# ACT_Lipoly_Charger_R3_FINAL.net
KiCad netlist of a schematic drawn in EAGLE
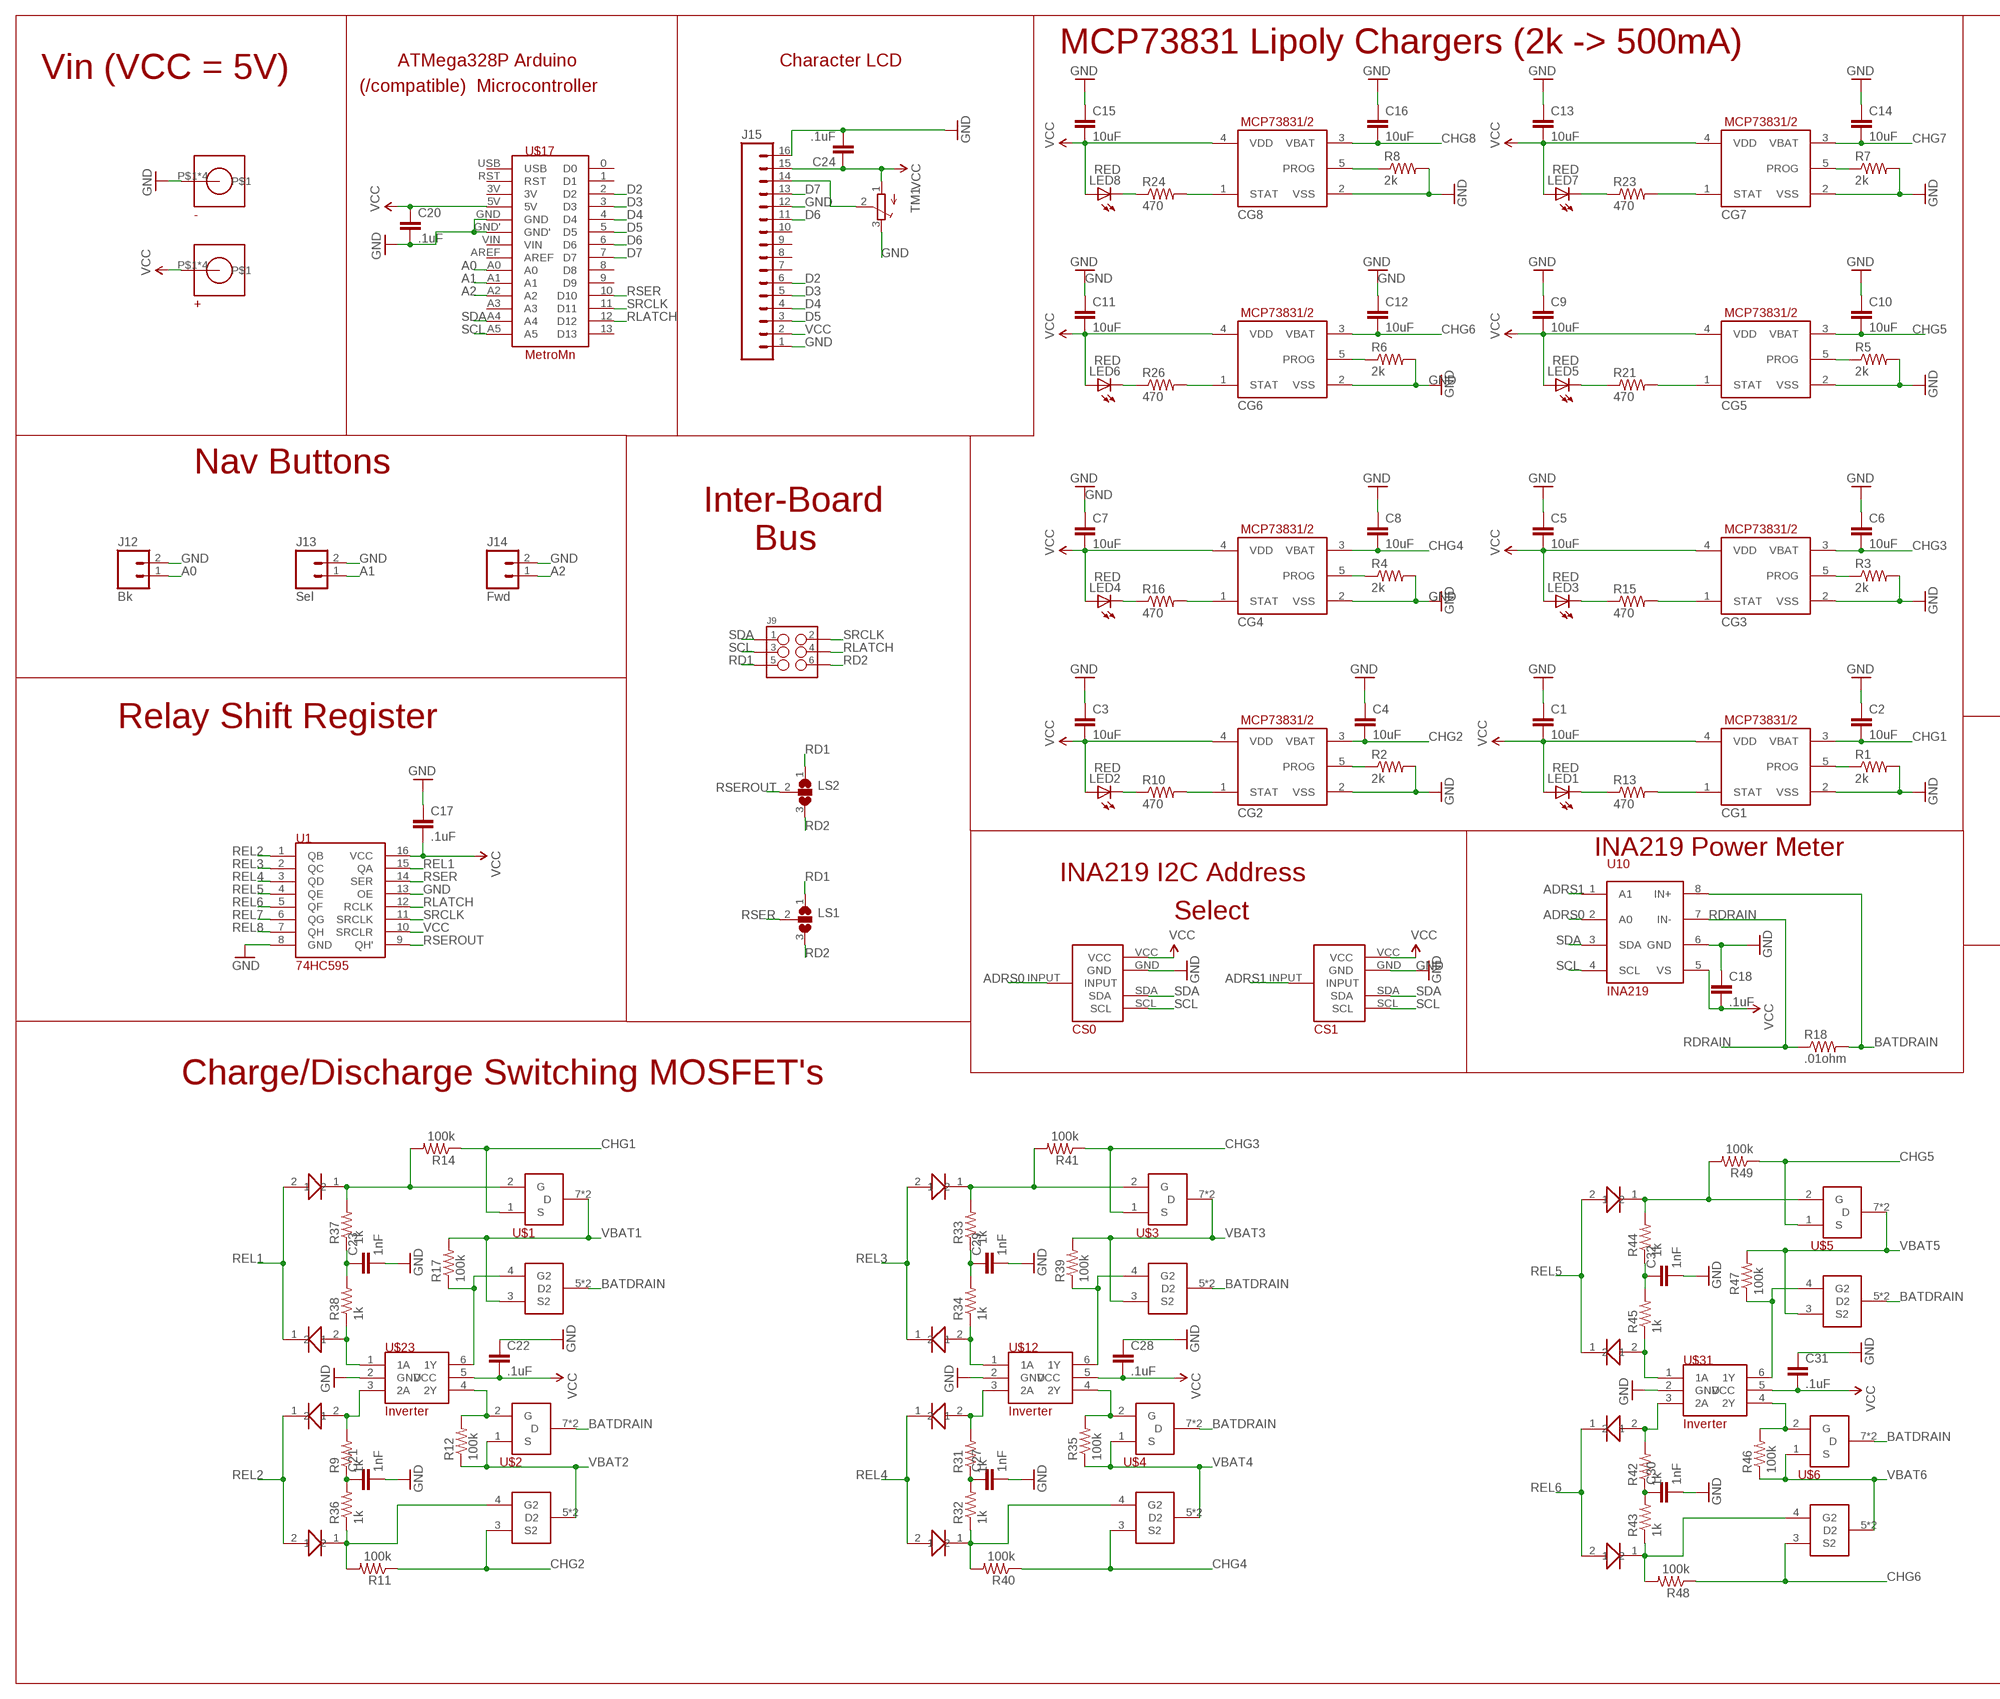
[diagram p0: schematic, sheet 1, part 1 of 2]
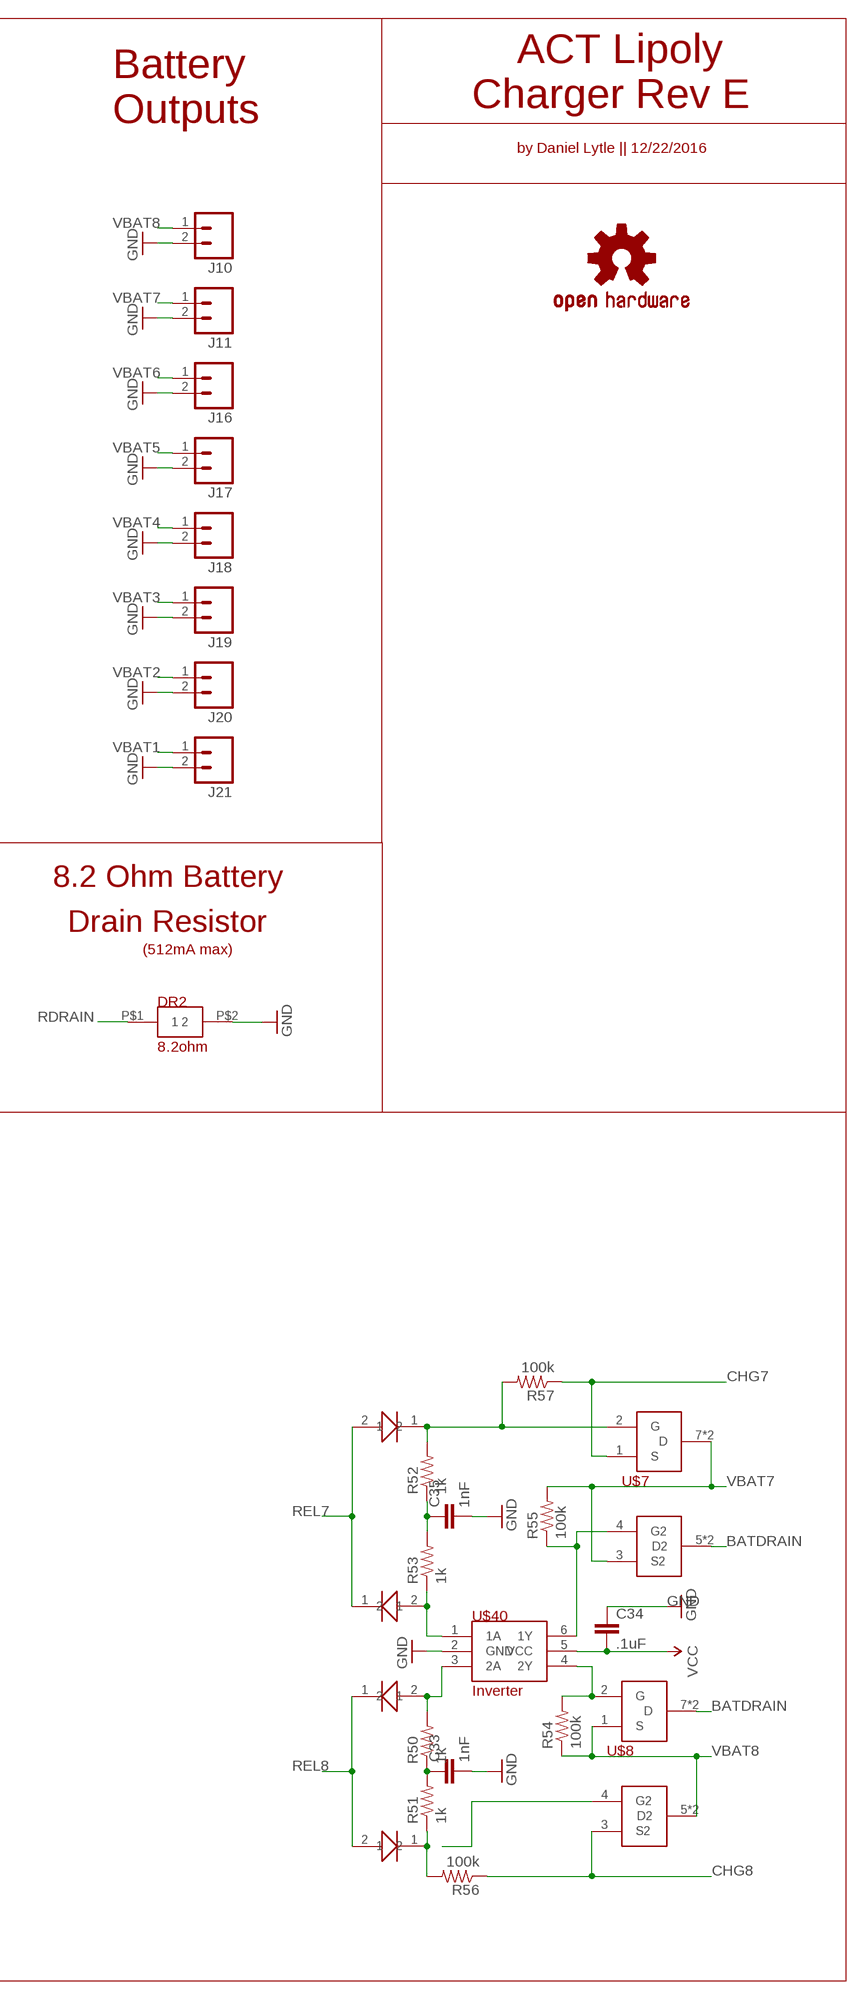
[diagram p1: schematic, sheet 1, part 2 of 2]

(export (version "E")
  (design (tool "Eeschema 10.0.6"))
  (components
    (comp (ref "+")
      (value "8191-SEMS")
      (footprint "eagle-import:9191-SEMS")
      (libsource (lib "eagle-import") (part "8191-SEMS"))
    )
    (comp (ref "-")
      (value "8191-SEMS")
      (footprint "eagle-import:9191-SEMS")
      (libsource (lib "eagle-import") (part "8191-SEMS"))
    )
    (comp (ref "C1")
      (value "10uF")
      (footprint "eagle-import:0805")
      (libsource (lib "eagle-import") (part "CAP0805"))
    )
    (comp (ref "C2")
      (value "10uF")
      (footprint "eagle-import:0805")
      (libsource (lib "eagle-import") (part "CAP0805"))
    )
    (comp (ref "C3")
      (value "10uF")
      (footprint "eagle-import:0805")
      (libsource (lib "eagle-import") (part "CAP0805"))
    )
    (comp (ref "C4")
      (value "10uF")
      (footprint "eagle-import:0805")
      (libsource (lib "eagle-import") (part "CAP0805"))
    )
    (comp (ref "C5")
      (value "10uF")
      (footprint "eagle-import:0805")
      (libsource (lib "eagle-import") (part "CAP0805"))
    )
    (comp (ref "C6")
      (value "10uF")
      (footprint "eagle-import:0805")
      (libsource (lib "eagle-import") (part "CAP0805"))
    )
    (comp (ref "C7")
      (value "10uF")
      (footprint "eagle-import:0805")
      (libsource (lib "eagle-import") (part "CAP0805"))
    )
    (comp (ref "C8")
      (value "10uF")
      (footprint "eagle-import:0805")
      (libsource (lib "eagle-import") (part "CAP0805"))
    )
    (comp (ref "C9")
      (value "10uF")
      (footprint "eagle-import:0805")
      (libsource (lib "eagle-import") (part "CAP0805"))
    )
    (comp (ref "C10")
      (value "10uF")
      (footprint "eagle-import:0805")
      (libsource (lib "eagle-import") (part "CAP0805"))
    )
    (comp (ref "C11")
      (value "10uF")
      (footprint "eagle-import:0805")
      (libsource (lib "eagle-import") (part "CAP0805"))
    )
    (comp (ref "C12")
      (value "10uF")
      (footprint "eagle-import:0805")
      (libsource (lib "eagle-import") (part "CAP0805"))
    )
    (comp (ref "C13")
      (value "10uF")
      (footprint "eagle-import:0805")
      (libsource (lib "eagle-import") (part "CAP0805"))
    )
    (comp (ref "C14")
      (value "10uF")
      (footprint "eagle-import:0805")
      (libsource (lib "eagle-import") (part "CAP0805"))
    )
    (comp (ref "C15")
      (value "10uF")
      (footprint "eagle-import:0805")
      (libsource (lib "eagle-import") (part "CAP0805"))
    )
    (comp (ref "C16")
      (value "10uF")
      (footprint "eagle-import:0805")
      (libsource (lib "eagle-import") (part "CAP0805"))
    )
    (comp (ref "C17")
      (value ".1uF")
      (footprint "eagle-import:0805")
      (libsource (lib "eagle-import") (part "CAP0805"))
    )
    (comp (ref "C18")
      (value ".1uF")
      (footprint "eagle-import:0805")
      (libsource (lib "eagle-import") (part "CAP0805"))
    )
    (comp (ref "C20")
      (value ".1uF")
      (footprint "eagle-import:0805")
      (libsource (lib "eagle-import") (part "CAP0805"))
    )
    (comp (ref "C21")
      (value "1nF")
      (footprint "eagle-import:0805")
      (libsource (lib "eagle-import") (part "SparkFun-Passives_CAP0805"))
    )
    (comp (ref "C22")
      (value ".1uF")
      (footprint "eagle-import:0805")
      (libsource (lib "eagle-import") (part "CAP0805"))
    )
    (comp (ref "C23")
      (value "1nF")
      (footprint "eagle-import:0805")
      (libsource (lib "eagle-import") (part "SparkFun-Passives_CAP0805"))
    )
    (comp (ref "C24")
      (value ".1uF")
      (footprint "eagle-import:0805")
      (libsource (lib "eagle-import") (part "CAP0805"))
    )
    (comp (ref "C27")
      (value "1nF")
      (footprint "eagle-import:0805")
      (libsource (lib "eagle-import") (part "SparkFun-Passives_CAP0805"))
    )
    (comp (ref "C28")
      (value ".1uF")
      (footprint "eagle-import:0805")
      (libsource (lib "eagle-import") (part "CAP0805"))
    )
    (comp (ref "C29")
      (value "1nF")
      (footprint "eagle-import:0805")
      (libsource (lib "eagle-import") (part "SparkFun-Passives_CAP0805"))
    )
    (comp (ref "C30")
      (value "1nF")
      (footprint "eagle-import:0805")
      (libsource (lib "eagle-import") (part "SparkFun-Passives_CAP0805"))
    )
    (comp (ref "C31")
      (value ".1uF")
      (footprint "eagle-import:0805")
      (libsource (lib "eagle-import") (part "CAP0805"))
    )
    (comp (ref "C32")
      (value "1nF")
      (footprint "eagle-import:0805")
      (libsource (lib "eagle-import") (part "SparkFun-Passives_CAP0805"))
    )
    (comp (ref "C33")
      (value "1nF")
      (footprint "eagle-import:0805")
      (libsource (lib "eagle-import") (part "SparkFun-Passives_CAP0805"))
    )
    (comp (ref "C34")
      (value ".1uF")
      (footprint "eagle-import:0805")
      (libsource (lib "eagle-import") (part "CAP0805"))
    )
    (comp (ref "C35")
      (value "1nF")
      (footprint "eagle-import:0805")
      (libsource (lib "eagle-import") (part "SparkFun-Passives_CAP0805"))
    )
    (comp (ref "CG1")
      (value "MCP73831/OT")
      (footprint "eagle-import:SOT23-5L")
      (libsource (lib "eagle-import") (part "MCP73831/OT"))
    )
    (comp (ref "CG2")
      (value "MCP73831/OT")
      (footprint "eagle-import:SOT23-5L")
      (libsource (lib "eagle-import") (part "MCP73831/OT"))
    )
    (comp (ref "CG3")
      (value "MCP73831/OT")
      (footprint "eagle-import:SOT23-5L")
      (libsource (lib "eagle-import") (part "MCP73831/OT"))
    )
    (comp (ref "CG4")
      (value "MCP73831/OT")
      (footprint "eagle-import:SOT23-5L")
      (libsource (lib "eagle-import") (part "MCP73831/OT"))
    )
    (comp (ref "CG5")
      (value "MCP73831/OT")
      (footprint "eagle-import:SOT23-5L")
      (libsource (lib "eagle-import") (part "MCP73831/OT"))
    )
    (comp (ref "CG6")
      (value "MCP73831/OT")
      (footprint "eagle-import:SOT23-5L")
      (libsource (lib "eagle-import") (part "MCP73831/OT"))
    )
    (comp (ref "CG7")
      (value "MCP73831/OT")
      (footprint "eagle-import:SOT23-5L")
      (libsource (lib "eagle-import") (part "MCP73831/OT"))
    )
    (comp (ref "CG8")
      (value "MCP73831/OT")
      (footprint "eagle-import:SOT23-5L")
      (libsource (lib "eagle-import") (part "MCP73831/OT"))
    )
    (comp (ref "CS0")
      (value "4-WAYSELECTOR")
      (footprint "eagle-import:4-WAYSELECTOR")
      (libsource (lib "eagle-import") (part "4-WAYSELECTOR"))
    )
    (comp (ref "CS1")
      (value "4-WAYSELECTOR")
      (footprint "eagle-import:4-WAYSELECTOR")
      (libsource (lib "eagle-import") (part "4-WAYSELECTOR"))
    )
    (comp (ref "DR2")
      (value "8.2ohm")
      (footprint "eagle-import:UB5C-5R6F1")
      (libsource (lib "eagle-import") (part "UB5C-5R6F1"))
    )
    (comp (ref "J9")
      (value "M03X2FEMALE")
      (footprint "eagle-import:2X3")
      (libsource (lib "eagle-import") (part "M03X2FEMALE"))
    )
    (comp (ref "J10")
      (value "M02LOCK_LONGPADS")
      (footprint "eagle-import:1X02_LOCK_LONGPADS")
      (libsource (lib "eagle-import") (part "M02LOCK_LONGPADS"))
    )
    (comp (ref "J11")
      (value "M02LOCK_LONGPADS")
      (footprint "eagle-import:1X02_LOCK_LONGPADS")
      (libsource (lib "eagle-import") (part "M02LOCK_LONGPADS"))
    )
    (comp (ref "J12")
      (value "Bk")
      (footprint "eagle-import:1X02_LOCK_LONGPADS")
      (libsource (lib "eagle-import") (part "M02LOCK_LONGPADS"))
    )
    (comp (ref "J13")
      (value "Sel")
      (footprint "eagle-import:1X02_LOCK_LONGPADS")
      (libsource (lib "eagle-import") (part "M02LOCK_LONGPADS"))
    )
    (comp (ref "J14")
      (value "Fwd")
      (footprint "eagle-import:1X02_LOCK_LONGPADS")
      (libsource (lib "eagle-import") (part "M02LOCK_LONGPADS"))
    )
    (comp (ref "J15")
      (value "M16LOCK_LONGPADS")
      (footprint "eagle-import:1X16_LOCK_LONGPADS")
      (libsource (lib "eagle-import") (part "M16LOCK_LONGPADS"))
    )
    (comp (ref "J16")
      (value "M02LOCK_LONGPADS")
      (footprint "eagle-import:1X02_LOCK_LONGPADS")
      (libsource (lib "eagle-import") (part "M02LOCK_LONGPADS"))
    )
    (comp (ref "J17")
      (value "M02LOCK_LONGPADS")
      (footprint "eagle-import:1X02_LOCK_LONGPADS")
      (libsource (lib "eagle-import") (part "M02LOCK_LONGPADS"))
    )
    (comp (ref "J18")
      (value "M02LOCK_LONGPADS")
      (footprint "eagle-import:1X02_LOCK_LONGPADS")
      (libsource (lib "eagle-import") (part "M02LOCK_LONGPADS"))
    )
    (comp (ref "J19")
      (value "M02LOCK_LONGPADS")
      (footprint "eagle-import:1X02_LOCK_LONGPADS")
      (libsource (lib "eagle-import") (part "M02LOCK_LONGPADS"))
    )
    (comp (ref "J20")
      (value "M02LOCK_LONGPADS")
      (footprint "eagle-import:1X02_LOCK_LONGPADS")
      (libsource (lib "eagle-import") (part "M02LOCK_LONGPADS"))
    )
    (comp (ref "J21")
      (value "M02LOCK_LONGPADS")
      (footprint "eagle-import:1X02_LOCK_LONGPADS")
      (libsource (lib "eagle-import") (part "M02LOCK_LONGPADS"))
    )
    (comp (ref "LED1")
      (value "RED")
      (footprint "eagle-import:CHIP-LED0805")
      (libsource (lib "eagle-import") (part "LEDCHIP-LED0805"))
    )
    (comp (ref "LED2")
      (value "RED")
      (footprint "eagle-import:CHIP-LED0805")
      (libsource (lib "eagle-import") (part "LEDCHIP-LED0805"))
    )
    (comp (ref "LED3")
      (value "RED")
      (footprint "eagle-import:CHIP-LED0805")
      (libsource (lib "eagle-import") (part "LEDCHIP-LED0805"))
    )
    (comp (ref "LED4")
      (value "RED")
      (footprint "eagle-import:CHIP-LED0805")
      (libsource (lib "eagle-import") (part "LEDCHIP-LED0805"))
    )
    (comp (ref "LED5")
      (value "RED")
      (footprint "eagle-import:CHIP-LED0805")
      (libsource (lib "eagle-import") (part "LEDCHIP-LED0805"))
    )
    (comp (ref "LED6")
      (value "RED")
      (footprint "eagle-import:CHIP-LED0805")
      (libsource (lib "eagle-import") (part "LEDCHIP-LED0805"))
    )
    (comp (ref "LED7")
      (value "RED")
      (footprint "eagle-import:CHIP-LED0805")
      (libsource (lib "eagle-import") (part "LEDCHIP-LED0805"))
    )
    (comp (ref "LED8")
      (value "RED")
      (footprint "eagle-import:CHIP-LED0805")
      (libsource (lib "eagle-import") (part "LEDCHIP-LED0805"))
    )
    (comp (ref "LS1")
      (value "SJ2W")
      (footprint "eagle-import:SJ_2")
      (libsource (lib "eagle-import") (part "SJ2W"))
    )
    (comp (ref "LS2")
      (value "SJ2W")
      (footprint "eagle-import:SJ_2")
      (libsource (lib "eagle-import") (part "SJ2W"))
    )
    (comp (ref "R1")
      (value "2k")
      (footprint "eagle-import:0805")
      (libsource (lib "eagle-import") (part "RESISTOR0805-RES"))
    )
    (comp (ref "R2")
      (value "2k")
      (footprint "eagle-import:0805")
      (libsource (lib "eagle-import") (part "RESISTOR0805-RES"))
    )
    (comp (ref "R3")
      (value "2k")
      (footprint "eagle-import:0805")
      (libsource (lib "eagle-import") (part "RESISTOR0805-RES"))
    )
    (comp (ref "R4")
      (value "2k")
      (footprint "eagle-import:0805")
      (libsource (lib "eagle-import") (part "RESISTOR0805-RES"))
    )
    (comp (ref "R5")
      (value "2k")
      (footprint "eagle-import:0805")
      (libsource (lib "eagle-import") (part "RESISTOR0805-RES"))
    )
    (comp (ref "R6")
      (value "2k")
      (footprint "eagle-import:0805")
      (libsource (lib "eagle-import") (part "RESISTOR0805-RES"))
    )
    (comp (ref "R7")
      (value "2k")
      (footprint "eagle-import:0805")
      (libsource (lib "eagle-import") (part "RESISTOR0805-RES"))
    )
    (comp (ref "R8")
      (value "2k")
      (footprint "eagle-import:0805")
      (libsource (lib "eagle-import") (part "RESISTOR0805-RES"))
    )
    (comp (ref "R9")
      (value "1k")
      (footprint "eagle-import:0805")
      (libsource (lib "eagle-import") (part "SparkFun-Resistors_RESISTOR0805-RES"))
    )
    (comp (ref "R10")
      (value "470")
      (footprint "eagle-import:0805")
      (libsource (lib "eagle-import") (part "RESISTOR0805-RES"))
    )
    (comp (ref "R11")
      (value "100k")
      (footprint "eagle-import:0805")
      (libsource (lib "eagle-import") (part "RESISTOR0805-RES"))
    )
    (comp (ref "R12")
      (value "100k")
      (footprint "eagle-import:0805")
      (libsource (lib "eagle-import") (part "RESISTOR0805-RES"))
    )
    (comp (ref "R13")
      (value "470")
      (footprint "eagle-import:0805")
      (libsource (lib "eagle-import") (part "RESISTOR0805-RES"))
    )
    (comp (ref "R14")
      (value "100k")
      (footprint "eagle-import:0805")
      (libsource (lib "eagle-import") (part "RESISTOR0805-RES"))
    )
    (comp (ref "R15")
      (value "470")
      (footprint "eagle-import:0805")
      (libsource (lib "eagle-import") (part "RESISTOR0805-RES"))
    )
    (comp (ref "R16")
      (value "470")
      (footprint "eagle-import:0805")
      (libsource (lib "eagle-import") (part "RESISTOR0805-RES"))
    )
    (comp (ref "R17")
      (value "100k")
      (footprint "eagle-import:0805")
      (libsource (lib "eagle-import") (part "RESISTOR0805-RES"))
    )
    (comp (ref "R18")
      (value ".01ohm")
      (footprint "eagle-import:0805")
      (libsource (lib "eagle-import") (part "RESISTOR0805-RES"))
    )
    (comp (ref "R21")
      (value "470")
      (footprint "eagle-import:0805")
      (libsource (lib "eagle-import") (part "RESISTOR0805-RES"))
    )
    (comp (ref "R23")
      (value "470")
      (footprint "eagle-import:0805")
      (libsource (lib "eagle-import") (part "RESISTOR0805-RES"))
    )
    (comp (ref "R24")
      (value "470")
      (footprint "eagle-import:0805")
      (libsource (lib "eagle-import") (part "RESISTOR0805-RES"))
    )
    (comp (ref "R26")
      (value "470")
      (footprint "eagle-import:0805")
      (libsource (lib "eagle-import") (part "RESISTOR0805-RES"))
    )
    (comp (ref "R31")
      (value "1k")
      (footprint "eagle-import:0805")
      (libsource (lib "eagle-import") (part "SparkFun-Resistors_RESISTOR0805-RES"))
    )
    (comp (ref "R32")
      (value "1k")
      (footprint "eagle-import:0805")
      (libsource (lib "eagle-import") (part "SparkFun-Resistors_RESISTOR0805-RES"))
    )
    (comp (ref "R33")
      (value "1k")
      (footprint "eagle-import:0805")
      (libsource (lib "eagle-import") (part "SparkFun-Resistors_RESISTOR0805-RES"))
    )
    (comp (ref "R34")
      (value "1k")
      (footprint "eagle-import:0805")
      (libsource (lib "eagle-import") (part "SparkFun-Resistors_RESISTOR0805-RES"))
    )
    (comp (ref "R35")
      (value "100k")
      (footprint "eagle-import:0805")
      (libsource (lib "eagle-import") (part "RESISTOR0805-RES"))
    )
    (comp (ref "R36")
      (value "1k")
      (footprint "eagle-import:0805")
      (libsource (lib "eagle-import") (part "SparkFun-Resistors_RESISTOR0805-RES"))
    )
    (comp (ref "R37")
      (value "1k")
      (footprint "eagle-import:0805")
      (libsource (lib "eagle-import") (part "SparkFun-Resistors_RESISTOR0805-RES"))
    )
    (comp (ref "R38")
      (value "1k")
      (footprint "eagle-import:0805")
      (libsource (lib "eagle-import") (part "SparkFun-Resistors_RESISTOR0805-RES"))
    )
    (comp (ref "R39")
      (value "100k")
      (footprint "eagle-import:0805")
      (libsource (lib "eagle-import") (part "RESISTOR0805-RES"))
    )
    (comp (ref "R40")
      (value "100k")
      (footprint "eagle-import:0805")
      (libsource (lib "eagle-import") (part "RESISTOR0805-RES"))
    )
    (comp (ref "R41")
      (value "100k")
      (footprint "eagle-import:0805")
      (libsource (lib "eagle-import") (part "RESISTOR0805-RES"))
    )
    (comp (ref "R42")
      (value "1k")
      (footprint "eagle-import:0805")
      (libsource (lib "eagle-import") (part "SparkFun-Resistors_RESISTOR0805-RES"))
    )
    (comp (ref "R43")
      (value "1k")
      (footprint "eagle-import:0805")
      (libsource (lib "eagle-import") (part "SparkFun-Resistors_RESISTOR0805-RES"))
    )
    (comp (ref "R44")
      (value "1k")
      (footprint "eagle-import:0805")
      (libsource (lib "eagle-import") (part "SparkFun-Resistors_RESISTOR0805-RES"))
    )
    (comp (ref "R45")
      (value "1k")
      (footprint "eagle-import:0805")
      (libsource (lib "eagle-import") (part "SparkFun-Resistors_RESISTOR0805-RES"))
    )
    (comp (ref "R46")
      (value "100k")
      (footprint "eagle-import:0805")
      (libsource (lib "eagle-import") (part "RESISTOR0805-RES"))
    )
    (comp (ref "R47")
      (value "100k")
      (footprint "eagle-import:0805")
      (libsource (lib "eagle-import") (part "RESISTOR0805-RES"))
    )
    (comp (ref "R48")
      (value "100k")
      (footprint "eagle-import:0805")
      (libsource (lib "eagle-import") (part "RESISTOR0805-RES"))
    )
    (comp (ref "R49")
      (value "100k")
      (footprint "eagle-import:0805")
      (libsource (lib "eagle-import") (part "RESISTOR0805-RES"))
    )
    (comp (ref "R50")
      (value "1k")
      (footprint "eagle-import:0805")
      (libsource (lib "eagle-import") (part "SparkFun-Resistors_RESISTOR0805-RES"))
    )
    (comp (ref "R51")
      (value "1k")
      (footprint "eagle-import:0805")
      (libsource (lib "eagle-import") (part "SparkFun-Resistors_RESISTOR0805-RES"))
    )
    (comp (ref "R52")
      (value "1k")
      (footprint "eagle-import:0805")
      (libsource (lib "eagle-import") (part "SparkFun-Resistors_RESISTOR0805-RES"))
    )
    (comp (ref "R53")
      (value "1k")
      (footprint "eagle-import:0805")
      (libsource (lib "eagle-import") (part "SparkFun-Resistors_RESISTOR0805-RES"))
    )
    (comp (ref "R54")
      (value "100k")
      (footprint "eagle-import:0805")
      (libsource (lib "eagle-import") (part "RESISTOR0805-RES"))
    )
    (comp (ref "R55")
      (value "100k")
      (footprint "eagle-import:0805")
      (libsource (lib "eagle-import") (part "RESISTOR0805-RES"))
    )
    (comp (ref "R56")
      (value "100k")
      (footprint "eagle-import:0805")
      (libsource (lib "eagle-import") (part "RESISTOR0805-RES"))
    )
    (comp (ref "R57")
      (value "100k")
      (footprint "eagle-import:0805")
      (libsource (lib "eagle-import") (part "RESISTOR0805-RES"))
    )
    (comp (ref "TM1")
      (value "TRIMPOTTC33X")
      (footprint "eagle-import:TC33X")
      (libsource (lib "eagle-import") (part "TRIMPOTTC33X"))
    )
    (comp (ref "U$1")
      (value "DMP3085LSD")
      (footprint "eagle-import:SOIC8")
      (libsource (lib "eagle-import") (part "DMP3085LSD"))
    )
    (comp (ref "U$2")
      (value "DMP3085LSD")
      (footprint "eagle-import:SOIC8")
      (libsource (lib "eagle-import") (part "DMP3085LSD"))
    )
    (comp (ref "U$3")
      (value "DMP3085LSD")
      (footprint "eagle-import:SOIC8")
      (libsource (lib "eagle-import") (part "DMP3085LSD"))
    )
    (comp (ref "U$4")
      (value "DMP3085LSD")
      (footprint "eagle-import:SOIC8")
      (libsource (lib "eagle-import") (part "DMP3085LSD"))
    )
    (comp (ref "U$5")
      (value "DMP3085LSD")
      (footprint "eagle-import:SOIC8")
      (libsource (lib "eagle-import") (part "DMP3085LSD"))
    )
    (comp (ref "U$6")
      (value "DMP3085LSD")
      (footprint "eagle-import:SOIC8")
      (libsource (lib "eagle-import") (part "DMP3085LSD"))
    )
    (comp (ref "U$7")
      (value "DMP3085LSD")
      (footprint "eagle-import:SOIC8")
      (libsource (lib "eagle-import") (part "DMP3085LSD"))
    )
    (comp (ref "U$8")
      (value "DMP3085LSD")
      (footprint "eagle-import:SOIC8")
      (libsource (lib "eagle-import") (part "DMP3085LSD"))
    )
    (comp (ref "U$12")
      (value "Inverter")
      (footprint "eagle-import:SOT363_PHILIPS")
      (libsource (lib "eagle-import") (part "TC7PZ14FU,LJ(CT_INVERTER"))
    )
    (comp (ref "U$15")
      (value "DA2J10100L_DIODE")
      (footprint "eagle-import:SOD323")
      (libsource (lib "eagle-import") (part "DA2J10100L_DIODE"))
    )
    (comp (ref "U$16")
      (value "DA2J10100L_DIODE")
      (footprint "eagle-import:SOD323")
      (libsource (lib "eagle-import") (part "DA2J10100L_DIODE"))
    )
    (comp (ref "U$17")
      (value "MetroMn")
      (footprint "eagle-import:ADAFRUIT_METRO_MINI")
      (libsource (lib "eagle-import") (part "ADAFRUIT_METRO_MINI"))
    )
    (comp (ref "U$18")
      (value "DA2J10100L_DIODE")
      (footprint "eagle-import:SOD323")
      (libsource (lib "eagle-import") (part "DA2J10100L_DIODE"))
    )
    (comp (ref "U$19")
      (value "DA2J10100L_DIODE")
      (footprint "eagle-import:SOD323")
      (libsource (lib "eagle-import") (part "DA2J10100L_DIODE"))
    )
    (comp (ref "U$23")
      (value "Inverter")
      (footprint "eagle-import:SOT363_PHILIPS")
      (libsource (lib "eagle-import") (part "TC7PZ14FU,LJ(CT_INVERTER"))
    )
    (comp (ref "U$26")
      (value "DA2J10100L_DIODE")
      (footprint "eagle-import:SOD323")
      (libsource (lib "eagle-import") (part "DA2J10100L_DIODE"))
    )
    (comp (ref "U$27")
      (value "DA2J10100L_DIODE")
      (footprint "eagle-import:SOD323")
      (libsource (lib "eagle-import") (part "DA2J10100L_DIODE"))
    )
    (comp (ref "U$28")
      (value "DA2J10100L_DIODE")
      (footprint "eagle-import:SOD323")
      (libsource (lib "eagle-import") (part "DA2J10100L_DIODE"))
    )
    (comp (ref "U$29")
      (value "DA2J10100L_DIODE")
      (footprint "eagle-import:SOD323")
      (libsource (lib "eagle-import") (part "DA2J10100L_DIODE"))
    )
    (comp (ref "U$31")
      (value "Inverter")
      (footprint "eagle-import:SOT363_PHILIPS")
      (libsource (lib "eagle-import") (part "TC7PZ14FU,LJ(CT_INVERTER"))
    )
    (comp (ref "U$34")
      (value "DA2J10100L_DIODE")
      (footprint "eagle-import:SOD323")
      (libsource (lib "eagle-import") (part "DA2J10100L_DIODE"))
    )
    (comp (ref "U$35")
      (value "DA2J10100L_DIODE")
      (footprint "eagle-import:SOD323")
      (libsource (lib "eagle-import") (part "DA2J10100L_DIODE"))
    )
    (comp (ref "U$36")
      (value "DA2J10100L_DIODE")
      (footprint "eagle-import:SOD323")
      (libsource (lib "eagle-import") (part "DA2J10100L_DIODE"))
    )
    (comp (ref "U$37")
      (value "DA2J10100L_DIODE")
      (footprint "eagle-import:SOD323")
      (libsource (lib "eagle-import") (part "DA2J10100L_DIODE"))
    )
    (comp (ref "U$40")
      (value "Inverter")
      (footprint "eagle-import:SOT363_PHILIPS")
      (libsource (lib "eagle-import") (part "TC7PZ14FU,LJ(CT_INVERTER"))
    )
    (comp (ref "U$43")
      (value "DA2J10100L_DIODE")
      (footprint "eagle-import:SOD323")
      (libsource (lib "eagle-import") (part "DA2J10100L_DIODE"))
    )
    (comp (ref "U$44")
      (value "DA2J10100L_DIODE")
      (footprint "eagle-import:SOD323")
      (libsource (lib "eagle-import") (part "DA2J10100L_DIODE"))
    )
    (comp (ref "U$45")
      (value "DA2J10100L_DIODE")
      (footprint "eagle-import:SOD323")
      (libsource (lib "eagle-import") (part "DA2J10100L_DIODE"))
    )
    (comp (ref "U$46")
      (value "DA2J10100L_DIODE")
      (footprint "eagle-import:SOD323")
      (libsource (lib "eagle-import") (part "DA2J10100L_DIODE"))
    )
    (comp (ref "U1")
      (value "74HC595")
      (footprint "eagle-import:DIL16")
      (libsource (lib "eagle-import") (part "74HC595"))
    )
    (comp (ref "U10")
      (value "INA219")
      (footprint "eagle-import:SOIC8")
      (libsource (lib "eagle-import") (part "INA219"))
    )
    (comp (ref "VCC")
      (value "OSHW-LOGOM-COPPER")
      (footprint "eagle-import:OSHW-LOGO-M_COPPER")
      (libsource (lib "eagle-import") (part "OSHW-LOGOM-COPPER"))
    )
  )
  (nets
    (net (code "1") (name "/A0") (class "Default")
      (node (ref "J12") (pin "1") (pinfunction "1_1") (pintype "passive"))
      (node (ref "U$17") (pin "A0") (pinfunction "A0_A0") (pintype "bidirectional"))
    )
    (net (code "2") (name "/A1") (class "Default")
      (node (ref "J13") (pin "1") (pinfunction "1_1") (pintype "passive"))
      (node (ref "U$17") (pin "A1") (pinfunction "A1_A1") (pintype "bidirectional"))
    )
    (net (code "3") (name "/A2") (class "Default")
      (node (ref "J14") (pin "1") (pinfunction "1_1") (pintype "passive"))
      (node (ref "U$17") (pin "A2") (pinfunction "A2_A2") (pintype "bidirectional"))
    )
    (net (code "4") (name "/ADRS0") (class "Default")
      (node (ref "CS0") (pin "INPUT") (pinfunction "INPUT_INPUT") (pintype "bidirectional"))
      (node (ref "U10") (pin "2") (pinfunction "A0_2") (pintype "input"))
    )
    (net (code "5") (name "/ADRS1") (class "Default")
      (node (ref "CS1") (pin "INPUT") (pinfunction "INPUT_INPUT") (pintype "bidirectional"))
      (node (ref "U10") (pin "1") (pinfunction "A1_1") (pintype "input"))
    )
    (net (code "6") (name "/BATDRAIN") (class "Default")
      (node (ref "R18") (pin "2") (pinfunction "2_2") (pintype "passive"))
      (node (ref "U$1") (pin "5") (pinfunction "D2_5") (pintype "bidirectional"))
      (node (ref "U$1") (pin "6") (pinfunction "D2_6") (pintype "bidirectional"))
      (node (ref "U$2") (pin "7") (pinfunction "D_7") (pintype "bidirectional"))
      (node (ref "U$2") (pin "8") (pinfunction "D_8") (pintype "bidirectional"))
      (node (ref "U$3") (pin "5") (pinfunction "D2_5") (pintype "bidirectional"))
      (node (ref "U$3") (pin "6") (pinfunction "D2_6") (pintype "bidirectional"))
      (node (ref "U$4") (pin "7") (pinfunction "D_7") (pintype "bidirectional"))
      (node (ref "U$4") (pin "8") (pinfunction "D_8") (pintype "bidirectional"))
      (node (ref "U$5") (pin "5") (pinfunction "D2_5") (pintype "bidirectional"))
      (node (ref "U$5") (pin "6") (pinfunction "D2_6") (pintype "bidirectional"))
      (node (ref "U$6") (pin "7") (pinfunction "D_7") (pintype "bidirectional"))
      (node (ref "U$6") (pin "8") (pinfunction "D_8") (pintype "bidirectional"))
      (node (ref "U$7") (pin "5") (pinfunction "D2_5") (pintype "bidirectional"))
      (node (ref "U$7") (pin "6") (pinfunction "D2_6") (pintype "bidirectional"))
      (node (ref "U$8") (pin "7") (pinfunction "D_7") (pintype "bidirectional"))
      (node (ref "U$8") (pin "8") (pinfunction "D_8") (pintype "bidirectional"))
      (node (ref "U10") (pin "8") (pinfunction "IN+_8") (pintype "input"))
    )
    (net (code "7") (name "/CHG1") (class "Default")
      (node (ref "C2") (pin "2") (pinfunction "2_2") (pintype "passive"))
      (node (ref "CG1") (pin "3") (pinfunction "VBAT_3") (pintype "bidirectional"))
      (node (ref "R14") (pin "1") (pinfunction "1_1") (pintype "passive"))
      (node (ref "U$1") (pin "1") (pinfunction "S_1") (pintype "bidirectional"))
    )
    (net (code "8") (name "/CHG2") (class "Default")
      (node (ref "C4") (pin "2") (pinfunction "2_2") (pintype "passive"))
      (node (ref "CG2") (pin "3") (pinfunction "VBAT_3") (pintype "bidirectional"))
      (node (ref "R11") (pin "1") (pinfunction "1_1") (pintype "passive"))
      (node (ref "U$2") (pin "3") (pinfunction "S2_3") (pintype "bidirectional"))
    )
    (net (code "9") (name "/CHG3") (class "Default")
      (node (ref "C6") (pin "2") (pinfunction "2_2") (pintype "passive"))
      (node (ref "CG3") (pin "3") (pinfunction "VBAT_3") (pintype "bidirectional"))
      (node (ref "R41") (pin "1") (pinfunction "1_1") (pintype "passive"))
      (node (ref "U$3") (pin "1") (pinfunction "S_1") (pintype "bidirectional"))
    )
    (net (code "10") (name "/CHG4") (class "Default")
      (node (ref "C8") (pin "2") (pinfunction "2_2") (pintype "passive"))
      (node (ref "CG4") (pin "3") (pinfunction "VBAT_3") (pintype "bidirectional"))
      (node (ref "R40") (pin "1") (pinfunction "1_1") (pintype "passive"))
      (node (ref "U$4") (pin "3") (pinfunction "S2_3") (pintype "bidirectional"))
    )
    (net (code "11") (name "/CHG5") (class "Default")
      (node (ref "C10") (pin "2") (pinfunction "2_2") (pintype "passive"))
      (node (ref "CG5") (pin "3") (pinfunction "VBAT_3") (pintype "bidirectional"))
      (node (ref "R49") (pin "1") (pinfunction "1_1") (pintype "passive"))
      (node (ref "U$5") (pin "1") (pinfunction "S_1") (pintype "bidirectional"))
    )
    (net (code "12") (name "/CHG6") (class "Default")
      (node (ref "C12") (pin "2") (pinfunction "2_2") (pintype "passive"))
      (node (ref "CG6") (pin "3") (pinfunction "VBAT_3") (pintype "bidirectional"))
      (node (ref "R48") (pin "1") (pinfunction "1_1") (pintype "passive"))
      (node (ref "U$6") (pin "3") (pinfunction "S2_3") (pintype "bidirectional"))
    )
    (net (code "13") (name "/CHG7") (class "Default")
      (node (ref "C14") (pin "2") (pinfunction "2_2") (pintype "passive"))
      (node (ref "CG7") (pin "3") (pinfunction "VBAT_3") (pintype "bidirectional"))
      (node (ref "R57") (pin "1") (pinfunction "1_1") (pintype "passive"))
      (node (ref "U$7") (pin "1") (pinfunction "S_1") (pintype "bidirectional"))
    )
    (net (code "14") (name "/CHG8") (class "Default")
      (node (ref "C16") (pin "2") (pinfunction "2_2") (pintype "passive"))
      (node (ref "CG8") (pin "3") (pinfunction "VBAT_3") (pintype "bidirectional"))
      (node (ref "R56") (pin "1") (pinfunction "1_1") (pintype "passive"))
      (node (ref "U$8") (pin "3") (pinfunction "S2_3") (pintype "bidirectional"))
    )
    (net (code "15") (name "/D2") (class "Default")
      (node (ref "J15") (pin "6") (pinfunction "6_6") (pintype "passive"))
      (node (ref "U$17") (pin "2") (pinfunction "D2_2") (pintype "bidirectional"))
    )
    (net (code "16") (name "/D3") (class "Default")
      (node (ref "J15") (pin "5") (pinfunction "5_5") (pintype "passive"))
      (node (ref "U$17") (pin "3") (pinfunction "D3_3") (pintype "bidirectional"))
    )
    (net (code "17") (name "/D4") (class "Default")
      (node (ref "J15") (pin "4") (pinfunction "4_4") (pintype "passive"))
      (node (ref "U$17") (pin "4") (pinfunction "D4_4") (pintype "bidirectional"))
    )
    (net (code "18") (name "/D5") (class "Default")
      (node (ref "J15") (pin "3") (pinfunction "3_3") (pintype "passive"))
      (node (ref "U$17") (pin "5") (pinfunction "D5_5") (pintype "bidirectional"))
    )
    (net (code "19") (name "/D6") (class "Default")
      (node (ref "J15") (pin "11") (pinfunction "11_11") (pintype "passive"))
      (node (ref "U$17") (pin "6") (pinfunction "D6_6") (pintype "bidirectional"))
    )
    (net (code "20") (name "/D7") (class "Default")
      (node (ref "J15") (pin "13") (pinfunction "13_13") (pintype "passive"))
      (node (ref "U$17") (pin "7") (pinfunction "D7_7") (pintype "bidirectional"))
    )
    (net (code "21") (name "/RD1") (class "Default")
      (node (ref "J9") (pin "5") (pinfunction "5_5") (pintype "bidirectional"))
      (node (ref "LS1") (pin "1") (pinfunction "1_1") (pintype "passive"))
      (node (ref "LS2") (pin "1") (pinfunction "1_1") (pintype "passive"))
    )
    (net (code "22") (name "/RD2") (class "Default")
      (node (ref "J9") (pin "6") (pinfunction "6_6") (pintype "bidirectional"))
      (node (ref "LS1") (pin "3") (pinfunction "3_3") (pintype "passive"))
      (node (ref "LS2") (pin "3") (pinfunction "3_3") (pintype "passive"))
    )
    (net (code "23") (name "/RDRAIN") (class "Default")
      (node (ref "DR2") (pin "P$1") (pinfunction "1_P$1") (pintype "bidirectional"))
      (node (ref "R18") (pin "1") (pinfunction "1_1") (pintype "passive"))
      (node (ref "U10") (pin "7") (pinfunction "IN-_7") (pintype "input"))
    )
    (net (code "24") (name "/REL1") (class "Default")
      (node (ref "U$27") (pin "2") (pinfunction "2_2") (pintype "bidirectional"))
      (node (ref "U$29") (pin "1") (pinfunction "1_1") (pintype "bidirectional"))
      (node (ref "U1") (pin "15") (pinfunction "QA_15") (pintype "bidirectional"))
    )
    (net (code "25") (name "/REL2") (class "Default")
      (node (ref "U$26") (pin "2") (pinfunction "2_2") (pintype "bidirectional"))
      (node (ref "U$28") (pin "1") (pinfunction "1_1") (pintype "bidirectional"))
      (node (ref "U1") (pin "1") (pinfunction "QB_1") (pintype "bidirectional"))
    )
    (net (code "26") (name "/REL3") (class "Default")
      (node (ref "U$18") (pin "2") (pinfunction "2_2") (pintype "bidirectional"))
      (node (ref "U$19") (pin "1") (pinfunction "1_1") (pintype "bidirectional"))
      (node (ref "U1") (pin "2") (pinfunction "QC_2") (pintype "bidirectional"))
    )
    (net (code "27") (name "/REL4") (class "Default")
      (node (ref "U$15") (pin "2") (pinfunction "2_2") (pintype "bidirectional"))
      (node (ref "U$16") (pin "1") (pinfunction "1_1") (pintype "bidirectional"))
      (node (ref "U1") (pin "3") (pinfunction "QD_3") (pintype "bidirectional"))
    )
    (net (code "28") (name "/REL5") (class "Default")
      (node (ref "U$36") (pin "2") (pinfunction "2_2") (pintype "bidirectional"))
      (node (ref "U$37") (pin "1") (pinfunction "1_1") (pintype "bidirectional"))
      (node (ref "U1") (pin "4") (pinfunction "QE_4") (pintype "bidirectional"))
    )
    (net (code "29") (name "/REL6") (class "Default")
      (node (ref "U$34") (pin "2") (pinfunction "2_2") (pintype "bidirectional"))
      (node (ref "U$35") (pin "1") (pinfunction "1_1") (pintype "bidirectional"))
      (node (ref "U1") (pin "5") (pinfunction "QF_5") (pintype "bidirectional"))
    )
    (net (code "30") (name "/REL7") (class "Default")
      (node (ref "U$45") (pin "2") (pinfunction "2_2") (pintype "bidirectional"))
      (node (ref "U$46") (pin "1") (pinfunction "1_1") (pintype "bidirectional"))
      (node (ref "U1") (pin "6") (pinfunction "QG_6") (pintype "bidirectional"))
    )
    (net (code "31") (name "/REL8") (class "Default")
      (node (ref "U$43") (pin "2") (pinfunction "2_2") (pintype "bidirectional"))
      (node (ref "U$44") (pin "1") (pinfunction "1_1") (pintype "bidirectional"))
      (node (ref "U1") (pin "7") (pinfunction "QH_7") (pintype "bidirectional"))
    )
    (net (code "32") (name "/RLATCH") (class "Default")
      (node (ref "J9") (pin "4") (pinfunction "4_4") (pintype "bidirectional"))
      (node (ref "U$17") (pin "12") (pinfunction "D12_12") (pintype "bidirectional"))
      (node (ref "U1") (pin "12") (pinfunction "RCLK_12") (pintype "bidirectional"))
    )
    (net (code "33") (name "/RSER") (class "Default")
      (node (ref "LS1") (pin "2") (pinfunction "2_2") (pintype "passive"))
      (node (ref "U$17") (pin "10") (pinfunction "D10_10") (pintype "bidirectional"))
      (node (ref "U1") (pin "14") (pinfunction "SER_14") (pintype "bidirectional"))
    )
    (net (code "34") (name "/RSEROUT") (class "Default")
      (node (ref "LS2") (pin "2") (pinfunction "2_2") (pintype "passive"))
      (node (ref "U1") (pin "9") (pinfunction "QH'_9") (pintype "bidirectional"))
    )
    (net (code "35") (name "/SCL") (class "Default")
      (node (ref "CS0") (pin "SCL") (pinfunction "SCL_SCL") (pintype "bidirectional"))
      (node (ref "CS1") (pin "SCL") (pinfunction "SCL_SCL") (pintype "bidirectional"))
      (node (ref "J9") (pin "3") (pinfunction "3_3") (pintype "bidirectional"))
      (node (ref "U$17") (pin "A5") (pinfunction "A5_A5") (pintype "bidirectional"))
      (node (ref "U10") (pin "4") (pinfunction "SCL_4") (pintype "input"))
    )
    (net (code "36") (name "/SDA") (class "Default")
      (node (ref "CS0") (pin "SDA") (pinfunction "SDA_SDA") (pintype "bidirectional"))
      (node (ref "CS1") (pin "SDA") (pinfunction "SDA_SDA") (pintype "bidirectional"))
      (node (ref "J9") (pin "1") (pinfunction "1_1") (pintype "bidirectional"))
      (node (ref "U$17") (pin "A4") (pinfunction "A4_A4") (pintype "bidirectional"))
      (node (ref "U10") (pin "3") (pinfunction "SDA_3") (pintype "bidirectional"))
    )
    (net (code "37") (name "/SRCLK") (class "Default")
      (node (ref "J9") (pin "2") (pinfunction "2_2") (pintype "bidirectional"))
      (node (ref "U$17") (pin "11") (pinfunction "D11_11") (pintype "bidirectional"))
      (node (ref "U1") (pin "11") (pinfunction "SRCLK_11") (pintype "bidirectional"))
    )
    (net (code "38") (name "/VBAT1") (class "Default")
      (node (ref "J21") (pin "1") (pinfunction "1_1") (pintype "passive"))
      (node (ref "R17") (pin "2") (pinfunction "2_2") (pintype "passive"))
      (node (ref "U$1") (pin "3") (pinfunction "S2_3") (pintype "bidirectional"))
      (node (ref "U$1") (pin "7") (pinfunction "D_7") (pintype "bidirectional"))
      (node (ref "U$1") (pin "8") (pinfunction "D_8") (pintype "bidirectional"))
    )
    (net (code "39") (name "/VBAT2") (class "Default")
      (node (ref "J20") (pin "1") (pinfunction "1_1") (pintype "passive"))
      (node (ref "R12") (pin "1") (pinfunction "1_1") (pintype "passive"))
      (node (ref "U$2") (pin "1") (pinfunction "S_1") (pintype "bidirectional"))
      (node (ref "U$2") (pin "5") (pinfunction "D2_5") (pintype "bidirectional"))
      (node (ref "U$2") (pin "6") (pinfunction "D2_6") (pintype "bidirectional"))
    )
    (net (code "40") (name "/VBAT3") (class "Default")
      (node (ref "J19") (pin "1") (pinfunction "1_1") (pintype "passive"))
      (node (ref "R39") (pin "2") (pinfunction "2_2") (pintype "passive"))
      (node (ref "U$3") (pin "3") (pinfunction "S2_3") (pintype "bidirectional"))
      (node (ref "U$3") (pin "7") (pinfunction "D_7") (pintype "bidirectional"))
      (node (ref "U$3") (pin "8") (pinfunction "D_8") (pintype "bidirectional"))
    )
    (net (code "41") (name "/VBAT4") (class "Default")
      (node (ref "J18") (pin "1") (pinfunction "1_1") (pintype "passive"))
      (node (ref "R35") (pin "1") (pinfunction "1_1") (pintype "passive"))
      (node (ref "U$4") (pin "1") (pinfunction "S_1") (pintype "bidirectional"))
      (node (ref "U$4") (pin "5") (pinfunction "D2_5") (pintype "bidirectional"))
      (node (ref "U$4") (pin "6") (pinfunction "D2_6") (pintype "bidirectional"))
    )
    (net (code "42") (name "/VBAT5") (class "Default")
      (node (ref "J17") (pin "1") (pinfunction "1_1") (pintype "passive"))
      (node (ref "R47") (pin "2") (pinfunction "2_2") (pintype "passive"))
      (node (ref "U$5") (pin "3") (pinfunction "S2_3") (pintype "bidirectional"))
      (node (ref "U$5") (pin "7") (pinfunction "D_7") (pintype "bidirectional"))
      (node (ref "U$5") (pin "8") (pinfunction "D_8") (pintype "bidirectional"))
    )
    (net (code "43") (name "/VBAT6") (class "Default")
      (node (ref "J16") (pin "1") (pinfunction "1_1") (pintype "passive"))
      (node (ref "R46") (pin "1") (pinfunction "1_1") (pintype "passive"))
      (node (ref "U$6") (pin "1") (pinfunction "S_1") (pintype "bidirectional"))
      (node (ref "U$6") (pin "5") (pinfunction "D2_5") (pintype "bidirectional"))
      (node (ref "U$6") (pin "6") (pinfunction "D2_6") (pintype "bidirectional"))
    )
    (net (code "44") (name "/VBAT7") (class "Default")
      (node (ref "J11") (pin "1") (pinfunction "1_1") (pintype "passive"))
      (node (ref "R55") (pin "2") (pinfunction "2_2") (pintype "passive"))
      (node (ref "U$7") (pin "3") (pinfunction "S2_3") (pintype "bidirectional"))
      (node (ref "U$7") (pin "7") (pinfunction "D_7") (pintype "bidirectional"))
      (node (ref "U$7") (pin "8") (pinfunction "D_8") (pintype "bidirectional"))
    )
    (net (code "45") (name "/VBAT8") (class "Default")
      (node (ref "J10") (pin "1") (pinfunction "1_1") (pintype "passive"))
      (node (ref "R54") (pin "1") (pinfunction "1_1") (pintype "passive"))
      (node (ref "U$8") (pin "1") (pinfunction "S_1") (pintype "bidirectional"))
      (node (ref "U$8") (pin "5") (pinfunction "D2_5") (pintype "bidirectional"))
      (node (ref "U$8") (pin "6") (pinfunction "D2_6") (pintype "bidirectional"))
    )
    (net (code "46") (name "GND") (class "Default")
      (node (ref "-") (pin "P$1") (pinfunction "P$1_P$1") (pintype "bidirectional"))
      (node (ref "-") (pin "P$2") (pinfunction "P$1_P$2") (pintype "bidirectional"))
      (node (ref "-") (pin "P$3") (pinfunction "P$1_P$3") (pintype "bidirectional"))
      (node (ref "-") (pin "P$4") (pinfunction "P$1_P$4") (pintype "bidirectional"))
      (node (ref "C1") (pin "1") (pinfunction "1_1") (pintype "passive"))
      (node (ref "C10") (pin "1") (pinfunction "1_1") (pintype "passive"))
      (node (ref "C11") (pin "1") (pinfunction "1_1") (pintype "passive"))
      (node (ref "C12") (pin "1") (pinfunction "1_1") (pintype "passive"))
      (node (ref "C13") (pin "1") (pinfunction "1_1") (pintype "passive"))
      (node (ref "C14") (pin "1") (pinfunction "1_1") (pintype "passive"))
      (node (ref "C15") (pin "1") (pinfunction "1_1") (pintype "passive"))
      (node (ref "C16") (pin "1") (pinfunction "1_1") (pintype "passive"))
      (node (ref "C17") (pin "1") (pinfunction "1_1") (pintype "passive"))
      (node (ref "C18") (pin "1") (pinfunction "1_1") (pintype "passive"))
      (node (ref "C2") (pin "1") (pinfunction "1_1") (pintype "passive"))
      (node (ref "C20") (pin "2") (pinfunction "2_2") (pintype "passive"))
      (node (ref "C21") (pin "2") (pinfunction "2_2") (pintype "passive"))
      (node (ref "C22") (pin "1") (pinfunction "1_1") (pintype "passive"))
      (node (ref "C23") (pin "2") (pinfunction "2_2") (pintype "passive"))
      (node (ref "C24") (pin "2") (pinfunction "2_2") (pintype "passive"))
      (node (ref "C27") (pin "2") (pinfunction "2_2") (pintype "passive"))
      (node (ref "C28") (pin "1") (pinfunction "1_1") (pintype "passive"))
      (node (ref "C29") (pin "2") (pinfunction "2_2") (pintype "passive"))
      (node (ref "C3") (pin "1") (pinfunction "1_1") (pintype "passive"))
      (node (ref "C30") (pin "2") (pinfunction "2_2") (pintype "passive"))
      (node (ref "C31") (pin "1") (pinfunction "1_1") (pintype "passive"))
      (node (ref "C32") (pin "2") (pinfunction "2_2") (pintype "passive"))
      (node (ref "C33") (pin "2") (pinfunction "2_2") (pintype "passive"))
      (node (ref "C34") (pin "1") (pinfunction "1_1") (pintype "passive"))
      (node (ref "C35") (pin "2") (pinfunction "2_2") (pintype "passive"))
      (node (ref "C4") (pin "1") (pinfunction "1_1") (pintype "passive"))
      (node (ref "C5") (pin "1") (pinfunction "1_1") (pintype "passive"))
      (node (ref "C6") (pin "1") (pinfunction "1_1") (pintype "passive"))
      (node (ref "C7") (pin "1") (pinfunction "1_1") (pintype "passive"))
      (node (ref "C8") (pin "1") (pinfunction "1_1") (pintype "passive"))
      (node (ref "C9") (pin "1") (pinfunction "1_1") (pintype "passive"))
      (node (ref "CG1") (pin "2") (pinfunction "VSS_2") (pintype "power_in"))
      (node (ref "CG2") (pin "2") (pinfunction "VSS_2") (pintype "power_in"))
      (node (ref "CG3") (pin "2") (pinfunction "VSS_2") (pintype "power_in"))
      (node (ref "CG4") (pin "2") (pinfunction "VSS_2") (pintype "power_in"))
      (node (ref "CG5") (pin "2") (pinfunction "VSS_2") (pintype "power_in"))
      (node (ref "CG6") (pin "2") (pinfunction "VSS_2") (pintype "power_in"))
      (node (ref "CG7") (pin "2") (pinfunction "VSS_2") (pintype "power_in"))
      (node (ref "CG8") (pin "2") (pinfunction "VSS_2") (pintype "power_in"))
      (node (ref "CS0") (pin "GND") (pinfunction "GND_GND") (pintype "bidirectional"))
      (node (ref "CS1") (pin "GND") (pinfunction "GND_GND") (pintype "bidirectional"))
      (node (ref "DR2") (pin "P$2") (pinfunction "2_P$2") (pintype "bidirectional"))
      (node (ref "J10") (pin "2") (pinfunction "2_2") (pintype "passive"))
      (node (ref "J11") (pin "2") (pinfunction "2_2") (pintype "passive"))
      (node (ref "J12") (pin "2") (pinfunction "2_2") (pintype "passive"))
      (node (ref "J13") (pin "2") (pinfunction "2_2") (pintype "passive"))
      (node (ref "J14") (pin "2") (pinfunction "2_2") (pintype "passive"))
      (node (ref "J15") (pin "1") (pinfunction "1_1") (pintype "passive"))
      (node (ref "J15") (pin "12") (pinfunction "12_12") (pintype "passive"))
      (node (ref "J15") (pin "16") (pinfunction "16_16") (pintype "passive"))
      (node (ref "J16") (pin "2") (pinfunction "2_2") (pintype "passive"))
      (node (ref "J17") (pin "2") (pinfunction "2_2") (pintype "passive"))
      (node (ref "J18") (pin "2") (pinfunction "2_2") (pintype "passive"))
      (node (ref "J19") (pin "2") (pinfunction "2_2") (pintype "passive"))
      (node (ref "J20") (pin "2") (pinfunction "2_2") (pintype "passive"))
      (node (ref "J21") (pin "2") (pinfunction "2_2") (pintype "passive"))
      (node (ref "R1") (pin "2") (pinfunction "2_2") (pintype "passive"))
      (node (ref "R2") (pin "2") (pinfunction "2_2") (pintype "passive"))
      (node (ref "R3") (pin "2") (pinfunction "2_2") (pintype "passive"))
      (node (ref "R4") (pin "2") (pinfunction "2_2") (pintype "passive"))
      (node (ref "R5") (pin "2") (pinfunction "2_2") (pintype "passive"))
      (node (ref "R6") (pin "2") (pinfunction "2_2") (pintype "passive"))
      (node (ref "R7") (pin "2") (pinfunction "2_2") (pintype "passive"))
      (node (ref "R8") (pin "2") (pinfunction "2_2") (pintype "passive"))
      (node (ref "TM1") (pin "3") (pinfunction "E_3") (pintype "passive"))
      (node (ref "U$12") (pin "2") (pinfunction "GND_2") (pintype "bidirectional"))
      (node (ref "U$17") (pin "GND") (pinfunction "GND_GND") (pintype "bidirectional"))
      (node (ref "U$17") (pin "GND'") (pinfunction "GND'_GND'") (pintype "bidirectional"))
      (node (ref "U$23") (pin "2") (pinfunction "GND_2") (pintype "bidirectional"))
      (node (ref "U$31") (pin "2") (pinfunction "GND_2") (pintype "bidirectional"))
      (node (ref "U$40") (pin "2") (pinfunction "GND_2") (pintype "bidirectional"))
      (node (ref "U1") (pin "13") (pinfunction "OE_13") (pintype "bidirectional"))
      (node (ref "U1") (pin "8") (pinfunction "GND_8") (pintype "bidirectional"))
      (node (ref "U10") (pin "6") (pinfunction "GND_6") (pintype "power_in"))
    )
    (net (code "47") (name "Net-(C21-Pad1)") (class "Default")
      (node (ref "C21") (pin "1") (pinfunction "1_1") (pintype "passive"))
      (node (ref "R36") (pin "2") (pinfunction "2_2") (pintype "passive"))
      (node (ref "R9") (pin "1") (pinfunction "1_1") (pintype "passive"))
    )
    (net (code "48") (name "Net-(C23-Pad1)") (class "Default")
      (node (ref "C23") (pin "1") (pinfunction "1_1") (pintype "passive"))
      (node (ref "R37") (pin "1") (pinfunction "1_1") (pintype "passive"))
      (node (ref "R38") (pin "2") (pinfunction "2_2") (pintype "passive"))
    )
    (net (code "49") (name "Net-(C27-Pad1)") (class "Default")
      (node (ref "C27") (pin "1") (pinfunction "1_1") (pintype "passive"))
      (node (ref "R31") (pin "1") (pinfunction "1_1") (pintype "passive"))
      (node (ref "R32") (pin "2") (pinfunction "2_2") (pintype "passive"))
    )
    (net (code "50") (name "Net-(C29-Pad1)") (class "Default")
      (node (ref "C29") (pin "1") (pinfunction "1_1") (pintype "passive"))
      (node (ref "R33") (pin "1") (pinfunction "1_1") (pintype "passive"))
      (node (ref "R34") (pin "2") (pinfunction "2_2") (pintype "passive"))
    )
    (net (code "51") (name "Net-(C30-Pad1)") (class "Default")
      (node (ref "C30") (pin "1") (pinfunction "1_1") (pintype "passive"))
      (node (ref "R42") (pin "1") (pinfunction "1_1") (pintype "passive"))
      (node (ref "R43") (pin "2") (pinfunction "2_2") (pintype "passive"))
    )
    (net (code "52") (name "Net-(C32-Pad1)") (class "Default")
      (node (ref "C32") (pin "1") (pinfunction "1_1") (pintype "passive"))
      (node (ref "R44") (pin "1") (pinfunction "1_1") (pintype "passive"))
      (node (ref "R45") (pin "2") (pinfunction "2_2") (pintype "passive"))
    )
    (net (code "53") (name "Net-(C33-Pad1)") (class "Default")
      (node (ref "C33") (pin "1") (pinfunction "1_1") (pintype "passive"))
      (node (ref "R50") (pin "1") (pinfunction "1_1") (pintype "passive"))
      (node (ref "R51") (pin "2") (pinfunction "2_2") (pintype "passive"))
    )
    (net (code "54") (name "Net-(C35-Pad1)") (class "Default")
      (node (ref "C35") (pin "1") (pinfunction "1_1") (pintype "passive"))
      (node (ref "R52") (pin "1") (pinfunction "1_1") (pintype "passive"))
      (node (ref "R53") (pin "2") (pinfunction "2_2") (pintype "passive"))
    )
    (net (code "55") (name "Net-(CG1-PROG)") (class "Default")
      (node (ref "CG1") (pin "5") (pinfunction "PROG_5") (pintype "input"))
      (node (ref "R1") (pin "1") (pinfunction "1_1") (pintype "passive"))
    )
    (net (code "56") (name "Net-(CG1-STAT)") (class "Default")
      (node (ref "CG1") (pin "1") (pinfunction "STAT_1") (pintype "output"))
      (node (ref "R13") (pin "2") (pinfunction "2_2") (pintype "passive"))
    )
    (net (code "57") (name "Net-(CG2-PROG)") (class "Default")
      (node (ref "CG2") (pin "5") (pinfunction "PROG_5") (pintype "input"))
      (node (ref "R2") (pin "1") (pinfunction "1_1") (pintype "passive"))
    )
    (net (code "58") (name "Net-(CG2-STAT)") (class "Default")
      (node (ref "CG2") (pin "1") (pinfunction "STAT_1") (pintype "output"))
      (node (ref "R10") (pin "2") (pinfunction "2_2") (pintype "passive"))
    )
    (net (code "59") (name "Net-(CG3-PROG)") (class "Default")
      (node (ref "CG3") (pin "5") (pinfunction "PROG_5") (pintype "input"))
      (node (ref "R3") (pin "1") (pinfunction "1_1") (pintype "passive"))
    )
    (net (code "60") (name "Net-(CG3-STAT)") (class "Default")
      (node (ref "CG3") (pin "1") (pinfunction "STAT_1") (pintype "output"))
      (node (ref "R15") (pin "2") (pinfunction "2_2") (pintype "passive"))
    )
    (net (code "61") (name "Net-(CG4-PROG)") (class "Default")
      (node (ref "CG4") (pin "5") (pinfunction "PROG_5") (pintype "input"))
      (node (ref "R4") (pin "1") (pinfunction "1_1") (pintype "passive"))
    )
    (net (code "62") (name "Net-(CG4-STAT)") (class "Default")
      (node (ref "CG4") (pin "1") (pinfunction "STAT_1") (pintype "output"))
      (node (ref "R16") (pin "2") (pinfunction "2_2") (pintype "passive"))
    )
    (net (code "63") (name "Net-(CG5-PROG)") (class "Default")
      (node (ref "CG5") (pin "5") (pinfunction "PROG_5") (pintype "input"))
      (node (ref "R5") (pin "1") (pinfunction "1_1") (pintype "passive"))
    )
    (net (code "64") (name "Net-(CG5-STAT)") (class "Default")
      (node (ref "CG5") (pin "1") (pinfunction "STAT_1") (pintype "output"))
      (node (ref "R21") (pin "2") (pinfunction "2_2") (pintype "passive"))
    )
    (net (code "65") (name "Net-(CG6-PROG)") (class "Default")
      (node (ref "CG6") (pin "5") (pinfunction "PROG_5") (pintype "input"))
      (node (ref "R6") (pin "1") (pinfunction "1_1") (pintype "passive"))
    )
    (net (code "66") (name "Net-(CG6-STAT)") (class "Default")
      (node (ref "CG6") (pin "1") (pinfunction "STAT_1") (pintype "output"))
      (node (ref "R26") (pin "2") (pinfunction "2_2") (pintype "passive"))
    )
    (net (code "67") (name "Net-(CG7-PROG)") (class "Default")
      (node (ref "CG7") (pin "5") (pinfunction "PROG_5") (pintype "input"))
      (node (ref "R7") (pin "1") (pinfunction "1_1") (pintype "passive"))
    )
    (net (code "68") (name "Net-(CG7-STAT)") (class "Default")
      (node (ref "CG7") (pin "1") (pinfunction "STAT_1") (pintype "output"))
      (node (ref "R23") (pin "2") (pinfunction "2_2") (pintype "passive"))
    )
    (net (code "69") (name "Net-(CG8-PROG)") (class "Default")
      (node (ref "CG8") (pin "5") (pinfunction "PROG_5") (pintype "input"))
      (node (ref "R8") (pin "1") (pinfunction "1_1") (pintype "passive"))
    )
    (net (code "70") (name "Net-(CG8-STAT)") (class "Default")
      (node (ref "CG8") (pin "1") (pinfunction "STAT_1") (pintype "output"))
      (node (ref "R24") (pin "2") (pinfunction "2_2") (pintype "passive"))
    )
    (net (code "71") (name "Net-(LED1-PadC)") (class "Default")
      (node (ref "LED1") (pin "C") (pinfunction "C_C") (pintype "passive"))
      (node (ref "R13") (pin "1") (pinfunction "1_1") (pintype "passive"))
    )
    (net (code "72") (name "Net-(LED2-PadC)") (class "Default")
      (node (ref "LED2") (pin "C") (pinfunction "C_C") (pintype "passive"))
      (node (ref "R10") (pin "1") (pinfunction "1_1") (pintype "passive"))
    )
    (net (code "73") (name "Net-(LED3-PadC)") (class "Default")
      (node (ref "LED3") (pin "C") (pinfunction "C_C") (pintype "passive"))
      (node (ref "R15") (pin "1") (pinfunction "1_1") (pintype "passive"))
    )
    (net (code "74") (name "Net-(LED4-PadC)") (class "Default")
      (node (ref "LED4") (pin "C") (pinfunction "C_C") (pintype "passive"))
      (node (ref "R16") (pin "1") (pinfunction "1_1") (pintype "passive"))
    )
    (net (code "75") (name "Net-(LED5-PadC)") (class "Default")
      (node (ref "LED5") (pin "C") (pinfunction "C_C") (pintype "passive"))
      (node (ref "R21") (pin "1") (pinfunction "1_1") (pintype "passive"))
    )
    (net (code "76") (name "Net-(LED6-PadC)") (class "Default")
      (node (ref "LED6") (pin "C") (pinfunction "C_C") (pintype "passive"))
      (node (ref "R26") (pin "1") (pinfunction "1_1") (pintype "passive"))
    )
    (net (code "77") (name "Net-(LED7-PadC)") (class "Default")
      (node (ref "LED7") (pin "C") (pinfunction "C_C") (pintype "passive"))
      (node (ref "R23") (pin "1") (pinfunction "1_1") (pintype "passive"))
    )
    (net (code "78") (name "Net-(LED8-PadC)") (class "Default")
      (node (ref "LED8") (pin "C") (pinfunction "C_C") (pintype "passive"))
      (node (ref "R24") (pin "1") (pinfunction "1_1") (pintype "passive"))
    )
    (net (code "79") (name "Net-(R51-Pad1)") (class "Default")
      (node (ref "R51") (pin "1") (pinfunction "1_1") (pintype "passive"))
      (node (ref "R56") (pin "2") (pinfunction "2_2") (pintype "passive"))
      (node (ref "U$43") (pin "1") (pinfunction "1_1") (pintype "bidirectional"))
    )
    (net (code "80") (name "Net-(TM1-S)") (class "Default")
      (node (ref "J15") (pin "14") (pinfunction "14_14") (pintype "passive"))
      (node (ref "TM1") (pin "2") (pinfunction "S_2") (pintype "passive"))
    )
    (net (code "81") (name "Net-(U$1-G)") (class "Default")
      (node (ref "R14") (pin "2") (pinfunction "2_2") (pintype "passive"))
      (node (ref "R37") (pin "2") (pinfunction "2_2") (pintype "passive"))
      (node (ref "U$1") (pin "2") (pinfunction "G_2") (pintype "bidirectional"))
      (node (ref "U$27") (pin "1") (pinfunction "1_1") (pintype "bidirectional"))
    )
    (net (code "82") (name "Net-(U$1-G2)") (class "Default")
      (node (ref "R17") (pin "1") (pinfunction "1_1") (pintype "passive"))
      (node (ref "U$1") (pin "4") (pinfunction "G2_4") (pintype "bidirectional"))
      (node (ref "U$23") (pin "6") (pinfunction "1Y_6") (pintype "bidirectional"))
    )
    (net (code "83") (name "Net-(U$2-G)") (class "Default")
      (node (ref "R12") (pin "2") (pinfunction "2_2") (pintype "passive"))
      (node (ref "U$2") (pin "2") (pinfunction "G_2") (pintype "bidirectional"))
      (node (ref "U$23") (pin "4") (pinfunction "2Y_4") (pintype "bidirectional"))
    )
    (net (code "84") (name "Net-(U$2-G2)") (class "Default")
      (node (ref "R11") (pin "2") (pinfunction "2_2") (pintype "passive"))
      (node (ref "R36") (pin "1") (pinfunction "1_1") (pintype "passive"))
      (node (ref "U$2") (pin "4") (pinfunction "G2_4") (pintype "bidirectional"))
      (node (ref "U$26") (pin "1") (pinfunction "1_1") (pintype "bidirectional"))
    )
    (net (code "85") (name "Net-(U$3-G)") (class "Default")
      (node (ref "R33") (pin "2") (pinfunction "2_2") (pintype "passive"))
      (node (ref "R41") (pin "2") (pinfunction "2_2") (pintype "passive"))
      (node (ref "U$18") (pin "1") (pinfunction "1_1") (pintype "bidirectional"))
      (node (ref "U$3") (pin "2") (pinfunction "G_2") (pintype "bidirectional"))
    )
    (net (code "86") (name "Net-(U$4-G2)") (class "Default")
      (node (ref "R32") (pin "1") (pinfunction "1_1") (pintype "passive"))
      (node (ref "R40") (pin "2") (pinfunction "2_2") (pintype "passive"))
      (node (ref "U$15") (pin "1") (pinfunction "1_1") (pintype "bidirectional"))
      (node (ref "U$4") (pin "4") (pinfunction "G2_4") (pintype "bidirectional"))
    )
    (net (code "87") (name "Net-(U$5-G)") (class "Default")
      (node (ref "R44") (pin "2") (pinfunction "2_2") (pintype "passive"))
      (node (ref "R49") (pin "2") (pinfunction "2_2") (pintype "passive"))
      (node (ref "U$36") (pin "1") (pinfunction "1_1") (pintype "bidirectional"))
      (node (ref "U$5") (pin "2") (pinfunction "G_2") (pintype "bidirectional"))
    )
    (net (code "88") (name "Net-(U$6-G2)") (class "Default")
      (node (ref "R43") (pin "1") (pinfunction "1_1") (pintype "passive"))
      (node (ref "R48") (pin "2") (pinfunction "2_2") (pintype "passive"))
      (node (ref "U$34") (pin "1") (pinfunction "1_1") (pintype "bidirectional"))
      (node (ref "U$6") (pin "4") (pinfunction "G2_4") (pintype "bidirectional"))
    )
    (net (code "89") (name "Net-(U$7-G)") (class "Default")
      (node (ref "R52") (pin "2") (pinfunction "2_2") (pintype "passive"))
      (node (ref "R57") (pin "2") (pinfunction "2_2") (pintype "passive"))
      (node (ref "U$45") (pin "1") (pinfunction "1_1") (pintype "bidirectional"))
      (node (ref "U$7") (pin "2") (pinfunction "G_2") (pintype "bidirectional"))
    )
    (net (code "90") (name "Net-(U$12-1A)") (class "Default")
      (node (ref "R34") (pin "1") (pinfunction "1_1") (pintype "passive"))
      (node (ref "U$12") (pin "1") (pinfunction "1A_1") (pintype "bidirectional"))
      (node (ref "U$19") (pin "2") (pinfunction "2_2") (pintype "bidirectional"))
    )
    (net (code "91") (name "Net-(U$12-1Y)") (class "Default")
      (node (ref "R39") (pin "1") (pinfunction "1_1") (pintype "passive"))
      (node (ref "U$12") (pin "6") (pinfunction "1Y_6") (pintype "bidirectional"))
      (node (ref "U$3") (pin "4") (pinfunction "G2_4") (pintype "bidirectional"))
    )
    (net (code "92") (name "Net-(U$12-2A)") (class "Default")
      (node (ref "R31") (pin "2") (pinfunction "2_2") (pintype "passive"))
      (node (ref "U$12") (pin "3") (pinfunction "2A_3") (pintype "bidirectional"))
      (node (ref "U$16") (pin "2") (pinfunction "2_2") (pintype "bidirectional"))
    )
    (net (code "93") (name "Net-(U$12-2Y)") (class "Default")
      (node (ref "R35") (pin "2") (pinfunction "2_2") (pintype "passive"))
      (node (ref "U$12") (pin "4") (pinfunction "2Y_4") (pintype "bidirectional"))
      (node (ref "U$4") (pin "2") (pinfunction "G_2") (pintype "bidirectional"))
    )
    (net (code "94") (name "Net-(U$23-1A)") (class "Default")
      (node (ref "R38") (pin "1") (pinfunction "1_1") (pintype "passive"))
      (node (ref "U$23") (pin "1") (pinfunction "1A_1") (pintype "bidirectional"))
      (node (ref "U$29") (pin "2") (pinfunction "2_2") (pintype "bidirectional"))
    )
    (net (code "95") (name "Net-(U$23-2A)") (class "Default")
      (node (ref "R9") (pin "2") (pinfunction "2_2") (pintype "passive"))
      (node (ref "U$23") (pin "3") (pinfunction "2A_3") (pintype "bidirectional"))
      (node (ref "U$28") (pin "2") (pinfunction "2_2") (pintype "bidirectional"))
    )
    (net (code "96") (name "Net-(U$31-1A)") (class "Default")
      (node (ref "R45") (pin "1") (pinfunction "1_1") (pintype "passive"))
      (node (ref "U$31") (pin "1") (pinfunction "1A_1") (pintype "bidirectional"))
      (node (ref "U$37") (pin "2") (pinfunction "2_2") (pintype "bidirectional"))
    )
    (net (code "97") (name "Net-(U$31-1Y)") (class "Default")
      (node (ref "R47") (pin "1") (pinfunction "1_1") (pintype "passive"))
      (node (ref "U$31") (pin "6") (pinfunction "1Y_6") (pintype "bidirectional"))
      (node (ref "U$5") (pin "4") (pinfunction "G2_4") (pintype "bidirectional"))
    )
    (net (code "98") (name "Net-(U$31-2A)") (class "Default")
      (node (ref "R42") (pin "2") (pinfunction "2_2") (pintype "passive"))
      (node (ref "U$31") (pin "3") (pinfunction "2A_3") (pintype "bidirectional"))
      (node (ref "U$35") (pin "2") (pinfunction "2_2") (pintype "bidirectional"))
    )
    (net (code "99") (name "Net-(U$31-2Y)") (class "Default")
      (node (ref "R46") (pin "2") (pinfunction "2_2") (pintype "passive"))
      (node (ref "U$31") (pin "4") (pinfunction "2Y_4") (pintype "bidirectional"))
      (node (ref "U$6") (pin "2") (pinfunction "G_2") (pintype "bidirectional"))
    )
    (net (code "100") (name "Net-(U$40-1A)") (class "Default")
      (node (ref "R53") (pin "1") (pinfunction "1_1") (pintype "passive"))
      (node (ref "U$40") (pin "1") (pinfunction "1A_1") (pintype "bidirectional"))
      (node (ref "U$46") (pin "2") (pinfunction "2_2") (pintype "bidirectional"))
    )
    (net (code "101") (name "Net-(U$40-1Y)") (class "Default")
      (node (ref "R55") (pin "1") (pinfunction "1_1") (pintype "passive"))
      (node (ref "U$40") (pin "6") (pinfunction "1Y_6") (pintype "bidirectional"))
      (node (ref "U$7") (pin "4") (pinfunction "G2_4") (pintype "bidirectional"))
    )
    (net (code "102") (name "Net-(U$40-2A)") (class "Default")
      (node (ref "R50") (pin "2") (pinfunction "2_2") (pintype "passive"))
      (node (ref "U$40") (pin "3") (pinfunction "2A_3") (pintype "bidirectional"))
      (node (ref "U$44") (pin "2") (pinfunction "2_2") (pintype "bidirectional"))
    )
    (net (code "103") (name "Net-(U$40-2Y)") (class "Default")
      (node (ref "R54") (pin "2") (pinfunction "2_2") (pintype "passive"))
      (node (ref "U$40") (pin "4") (pinfunction "2Y_4") (pintype "bidirectional"))
      (node (ref "U$8") (pin "2") (pinfunction "G_2") (pintype "bidirectional"))
    )
    (net (code "104") (name "VCC") (class "Default")
      (node (ref "+") (pin "P$1") (pinfunction "P$1_P$1") (pintype "bidirectional"))
      (node (ref "+") (pin "P$2") (pinfunction "P$1_P$2") (pintype "bidirectional"))
      (node (ref "+") (pin "P$3") (pinfunction "P$1_P$3") (pintype "bidirectional"))
      (node (ref "+") (pin "P$4") (pinfunction "P$1_P$4") (pintype "bidirectional"))
      (node (ref "C1") (pin "2") (pinfunction "2_2") (pintype "passive"))
      (node (ref "C11") (pin "2") (pinfunction "2_2") (pintype "passive"))
      (node (ref "C13") (pin "2") (pinfunction "2_2") (pintype "passive"))
      (node (ref "C15") (pin "2") (pinfunction "2_2") (pintype "passive"))
      (node (ref "C17") (pin "2") (pinfunction "2_2") (pintype "passive"))
      (node (ref "C18") (pin "2") (pinfunction "2_2") (pintype "passive"))
      (node (ref "C20") (pin "1") (pinfunction "1_1") (pintype "passive"))
      (node (ref "C22") (pin "2") (pinfunction "2_2") (pintype "passive"))
      (node (ref "C24") (pin "1") (pinfunction "1_1") (pintype "passive"))
      (node (ref "C28") (pin "2") (pinfunction "2_2") (pintype "passive"))
      (node (ref "C3") (pin "2") (pinfunction "2_2") (pintype "passive"))
      (node (ref "C31") (pin "2") (pinfunction "2_2") (pintype "passive"))
      (node (ref "C34") (pin "2") (pinfunction "2_2") (pintype "passive"))
      (node (ref "C5") (pin "2") (pinfunction "2_2") (pintype "passive"))
      (node (ref "C7") (pin "2") (pinfunction "2_2") (pintype "passive"))
      (node (ref "C9") (pin "2") (pinfunction "2_2") (pintype "passive"))
      (node (ref "CG1") (pin "4") (pinfunction "VDD_4") (pintype "power_in"))
      (node (ref "CG2") (pin "4") (pinfunction "VDD_4") (pintype "power_in"))
      (node (ref "CG3") (pin "4") (pinfunction "VDD_4") (pintype "power_in"))
      (node (ref "CG4") (pin "4") (pinfunction "VDD_4") (pintype "power_in"))
      (node (ref "CG5") (pin "4") (pinfunction "VDD_4") (pintype "power_in"))
      (node (ref "CG6") (pin "4") (pinfunction "VDD_4") (pintype "power_in"))
      (node (ref "CG7") (pin "4") (pinfunction "VDD_4") (pintype "power_in"))
      (node (ref "CG8") (pin "4") (pinfunction "VDD_4") (pintype "power_in"))
      (node (ref "CS0") (pin "VCC") (pinfunction "VCC_VCC") (pintype "bidirectional"))
      (node (ref "CS1") (pin "VCC") (pinfunction "VCC_VCC") (pintype "bidirectional"))
      (node (ref "J15") (pin "15") (pinfunction "15_15") (pintype "passive"))
      (node (ref "J15") (pin "2") (pinfunction "2_2") (pintype "passive"))
      (node (ref "LED1") (pin "A") (pinfunction "A_A") (pintype "passive"))
      (node (ref "LED2") (pin "A") (pinfunction "A_A") (pintype "passive"))
      (node (ref "LED3") (pin "A") (pinfunction "A_A") (pintype "passive"))
      (node (ref "LED4") (pin "A") (pinfunction "A_A") (pintype "passive"))
      (node (ref "LED5") (pin "A") (pinfunction "A_A") (pintype "passive"))
      (node (ref "LED6") (pin "A") (pinfunction "A_A") (pintype "passive"))
      (node (ref "LED7") (pin "A") (pinfunction "A_A") (pintype "passive"))
      (node (ref "LED8") (pin "A") (pinfunction "A_A") (pintype "passive"))
      (node (ref "TM1") (pin "1") (pinfunction "A_1") (pintype "passive"))
      (node (ref "U$12") (pin "5") (pinfunction "VCC_5") (pintype "bidirectional"))
      (node (ref "U$17") (pin "5V") (pinfunction "5V_5V") (pintype "bidirectional"))
      (node (ref "U$23") (pin "5") (pinfunction "VCC_5") (pintype "bidirectional"))
      (node (ref "U$31") (pin "5") (pinfunction "VCC_5") (pintype "bidirectional"))
      (node (ref "U$40") (pin "5") (pinfunction "VCC_5") (pintype "bidirectional"))
      (node (ref "U1") (pin "10") (pinfunction "SRCLR_10") (pintype "bidirectional"))
      (node (ref "U1") (pin "16") (pinfunction "VCC_16") (pintype "bidirectional"))
      (node (ref "U10") (pin "5") (pinfunction "VS_5") (pintype "power_in"))
    )
    (net (code "105") (name "unconnected-(J15-Pad7)") (class "Default")
      (node (ref "J15") (pin "7") (pinfunction "7_7") (pintype "passive"))
    )
    (net (code "106") (name "unconnected-(J15-Pad8)") (class "Default")
      (node (ref "J15") (pin "8") (pinfunction "8_8") (pintype "passive"))
    )
    (net (code "107") (name "unconnected-(J15-Pad9)") (class "Default")
      (node (ref "J15") (pin "9") (pinfunction "9_9") (pintype "passive"))
    )
    (net (code "108") (name "unconnected-(J15-Pad10)") (class "Default")
      (node (ref "J15") (pin "10") (pinfunction "10_10") (pintype "passive"))
    )
    (net (code "109") (name "unconnected-(U$8-G2-Pad4)") (class "Default")
      (node (ref "U$8") (pin "4") (pinfunction "G2_4") (pintype "bidirectional"))
    )
    (net (code "110") (name "unconnected-(U$17-D0-Pad0)") (class "Default")
      (node (ref "U$17") (pin "0") (pinfunction "D0_0") (pintype "bidirectional"))
    )
    (net (code "111") (name "unconnected-(U$17-D1-Pad1)") (class "Default")
      (node (ref "U$17") (pin "1") (pinfunction "D1_1") (pintype "bidirectional"))
    )
    (net (code "112") (name "unconnected-(U$17-D8-Pad8)") (class "Default")
      (node (ref "U$17") (pin "8") (pinfunction "D8_8") (pintype "bidirectional"))
    )
    (net (code "113") (name "unconnected-(U$17-D9-Pad9)") (class "Default")
      (node (ref "U$17") (pin "9") (pinfunction "D9_9") (pintype "bidirectional"))
    )
    (net (code "114") (name "unconnected-(U$17-D13-Pad13)") (class "Default")
      (node (ref "U$17") (pin "13") (pinfunction "D13_13") (pintype "bidirectional"))
    )
    (net (code "115") (name "unconnected-(U$17-Pad3V)") (class "Default")
      (node (ref "U$17") (pin "3V") (pinfunction "3V_3V") (pintype "bidirectional"))
    )
    (net (code "116") (name "unconnected-(U$17-PadA3)") (class "Default")
      (node (ref "U$17") (pin "A3") (pinfunction "A3_A3") (pintype "bidirectional"))
    )
    (net (code "117") (name "unconnected-(U$17-PadAREF)") (class "Default")
      (node (ref "U$17") (pin "AREF") (pinfunction "AREF_AREF") (pintype "bidirectional"))
    )
    (net (code "118") (name "unconnected-(U$17-PadRST)") (class "Default")
      (node (ref "U$17") (pin "RST") (pinfunction "RST_RST") (pintype "bidirectional"))
    )
    (net (code "119") (name "unconnected-(U$17-PadUSB)") (class "Default")
      (node (ref "U$17") (pin "USB") (pinfunction "USB_USB") (pintype "bidirectional"))
    )
    (net (code "120") (name "unconnected-(U$17-PadVIN)") (class "Default")
      (node (ref "U$17") (pin "VIN") (pinfunction "VIN_VIN") (pintype "bidirectional"))
    )
  )
)
